# MicroPhone.net
KiCad netlist of a schematic drawn in EasyEDA Pro
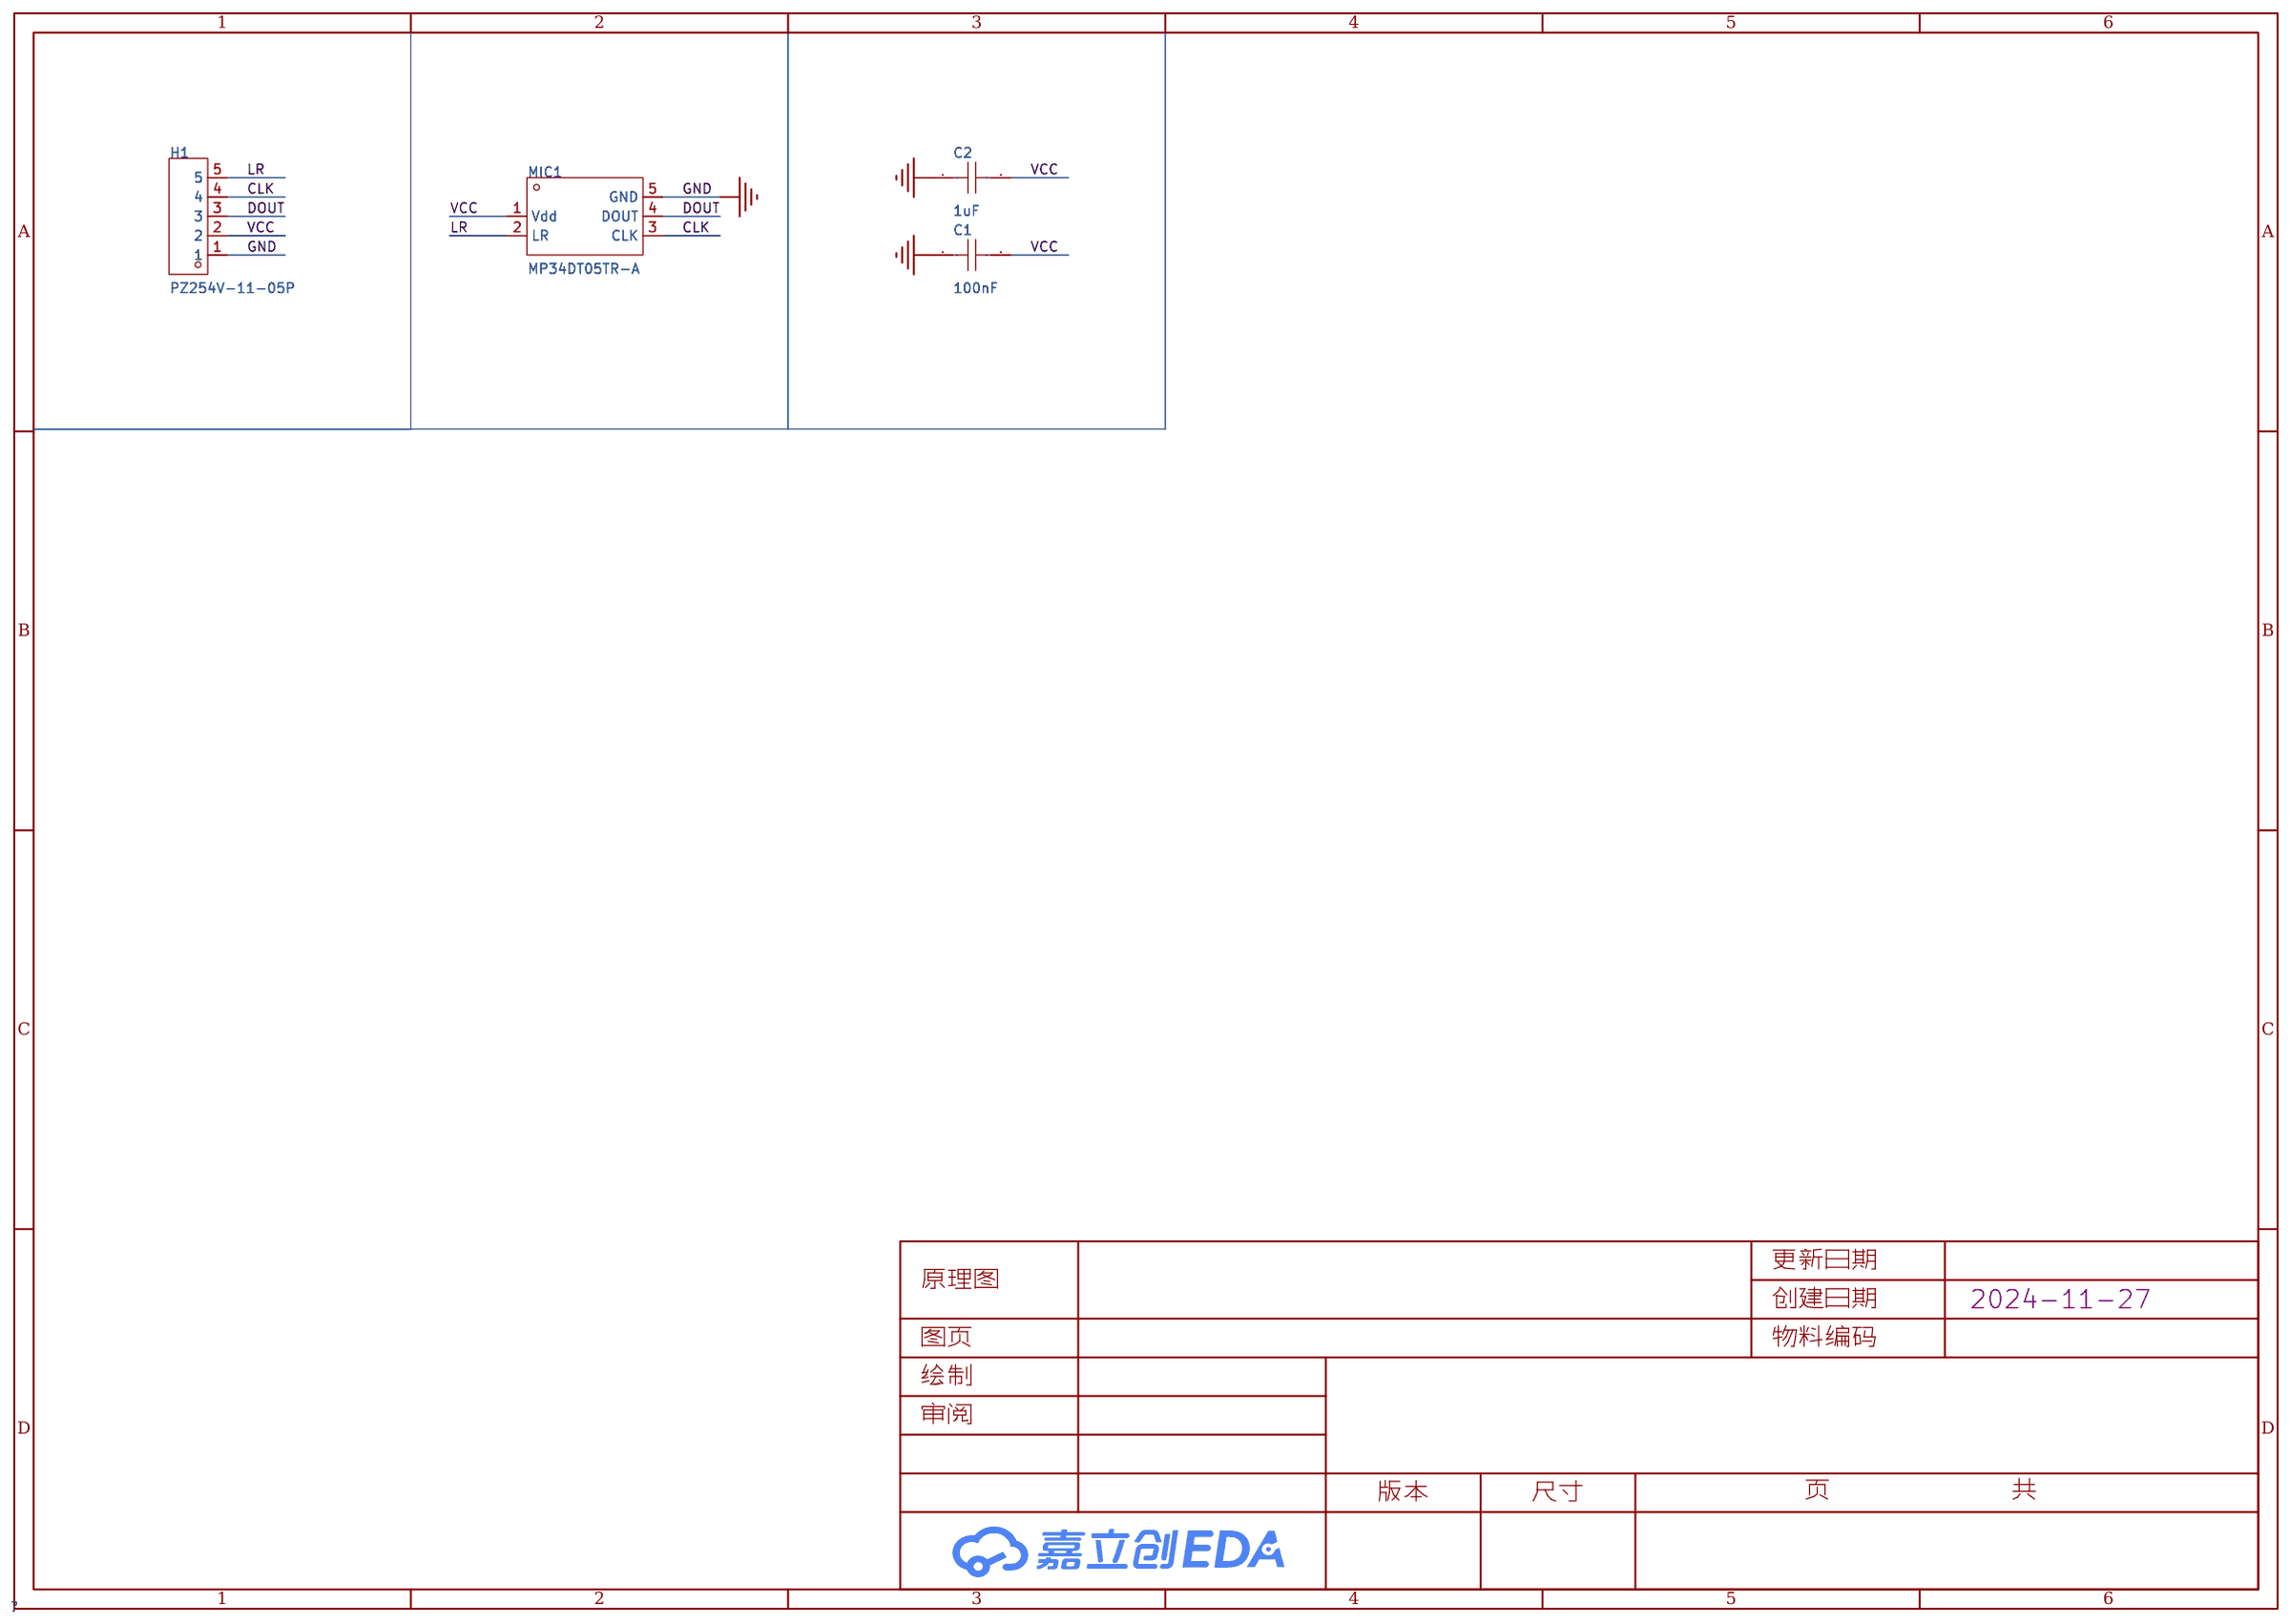
[diagram p0: schematic sheet]

(export (version "E")
  (design (tool "Eeschema 10.0.6"))
  (components
    (comp (ref "C1")
      (value "100nF")
      (footprint "easyedapro:C0603")
      (description "容值:100nF;精度:±10%;额定电压:50V;材质(温度系数):X7R;")
      (fields
        (field (name "Manufacturer Part") "CGA0603X7R104K500JT")
        (field (name "Manufacturer") "HRE(芯声)")
      )
      (libsource (lib "easyedapro") (part "CGA0603X7R104K500JT"))
    )
    (comp (ref "C2")
      (value "1uF")
      (footprint "easyedapro:C0603")
      (description "容值:1uF;精度:±10%;额定电压:16V;材质(温度系数):X5R;")
      (fields
        (field (name "Manufacturer Part") "CGA0603X5R105K160JT")
        (field (name "Manufacturer") "HRE(芯声)")
      )
      (libsource (lib "easyedapro") (part "CGA0603X5R105K160JT"))
    )
    (comp (ref "H1")
      (value "PZ254V-11-05P")
      (footprint "easyedapro:HDR-TH_5P-P2.54-V-M")
      (fields (field (name "Manufacturer") "XFCN(兴飞)"))
      (libsource (lib "easyedapro") (part "PZ254V-11-05P"))
    )
    (comp (ref "MIC1")
      (value "MP34DT05TR-A")
      (footprint "easyedapro:MIC-SMD_5P-L3.0-W4.0-P0.85-BL")
      (description "方向:全指向;信噪比:64dB;灵敏度:-26dB;阻抗:-;")
      (fields (field (name "Manufacturer") "ST(意法半导体)"))
      (libsource (lib "easyedapro") (part "MP34DT05TR-A"))
    )
  )
  (nets
    (net (code "1") (name "/CLK") (class "Default")
      (node (ref "H1") (pin "4") (pinfunction "4_4") (pintype "unspecified"))
      (node (ref "MIC1") (pin "3") (pinfunction "CLK_3") (pintype "unspecified"))
    )
    (net (code "2") (name "/DOUT") (class "Default")
      (node (ref "H1") (pin "3") (pinfunction "3_3") (pintype "unspecified"))
      (node (ref "MIC1") (pin "4") (pinfunction "DOUT_4") (pintype "unspecified"))
    )
    (net (code "3") (name "/LR") (class "Default")
      (node (ref "H1") (pin "5") (pinfunction "5_5") (pintype "unspecified"))
      (node (ref "MIC1") (pin "2") (pinfunction "LR_2") (pintype "unspecified"))
    )
    (net (code "4") (name "/VCC") (class "Default")
      (node (ref "C1") (pin "2") (pinfunction "2_2") (pintype "unspecified"))
      (node (ref "C2") (pin "2") (pinfunction "2_2") (pintype "unspecified"))
      (node (ref "H1") (pin "2") (pinfunction "2_2") (pintype "unspecified"))
      (node (ref "MIC1") (pin "1") (pinfunction "Vdd_1") (pintype "unspecified"))
    )
    (net (code "5") (name "GND") (class "Default")
      (node (ref "C1") (pin "1") (pinfunction "1_1") (pintype "unspecified"))
      (node (ref "C2") (pin "1") (pinfunction "1_1") (pintype "unspecified"))
      (node (ref "H1") (pin "1") (pinfunction "1_1") (pintype "unspecified"))
      (node (ref "MIC1") (pin "5") (pinfunction "GND_5") (pintype "unspecified"))
    )
  )
)
